# PortBreakoutCapacitive_r4_no_user.net
KiCad netlist of a schematic drawn in EAGLE
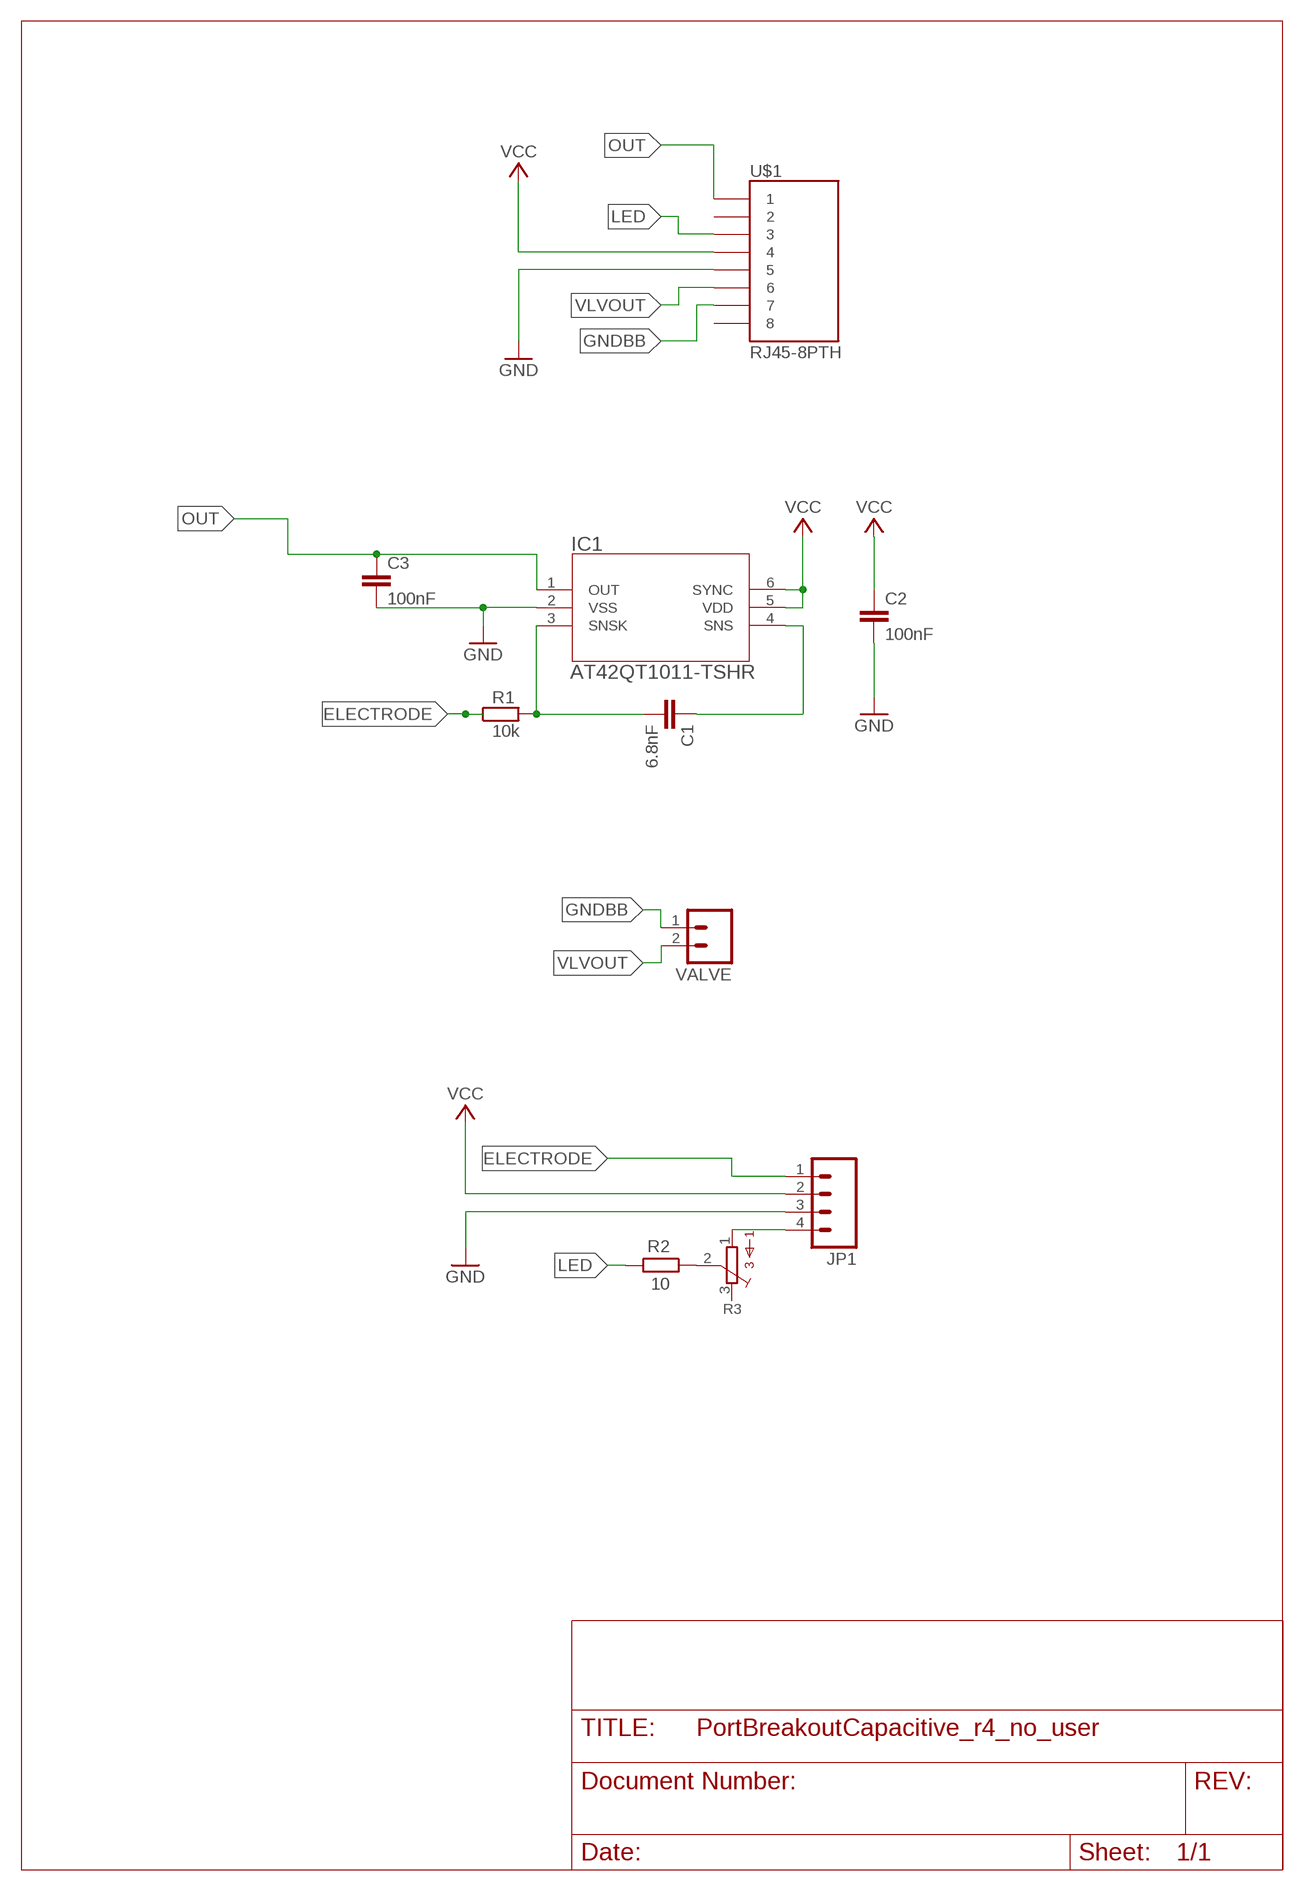
[diagram p0: schematic, sheet 1]

(export (version "E")
  (design (tool "Eeschema 10.0.6"))
  (components
    (comp (ref "C1")
      (value "6.8nF")
      (footprint "eagle-import:C1206")
      (libsource (lib "eagle-import") (part "C-EUC1206"))
    )
    (comp (ref "C2")
      (value "100nF")
      (footprint "eagle-import:C1206")
      (libsource (lib "eagle-import") (part "C-EUC1206"))
    )
    (comp (ref "C3")
      (value "100nF")
      (footprint "eagle-import:C1206")
      (libsource (lib "eagle-import") (part "C-EUC1206"))
    )
    (comp (ref "IC1")
      (value "AT42QT1011-TSHR")
      (footprint "eagle-import:6ST1_ATM")
      (fields (field (name "MANUFACTURER_PART_NUMBER") "AT42QT1010-TSHR"))
      (libsource (lib "eagle-import") (part "AT42QT1010-TSHR"))
    )
    (comp (ref "JP1")
      (value "CONN_04SCREW")
      (footprint "eagle-import:SCREWTERMINAL-3.5MM-4")
      (libsource (lib "eagle-import") (part "CONN_04SCREW"))
    )
    (comp (ref "R1")
      (value "10k")
      (footprint "eagle-import:R1206")
      (libsource (lib "eagle-import") (part "R-EU_R1206"))
    )
    (comp (ref "R2")
      (value "10")
      (footprint "eagle-import:R1206")
      (libsource (lib "eagle-import") (part "R-EU_R1206"))
    )
    (comp (ref "R3")
      (value "3362R")
      (footprint "eagle-import:3362R")
      (libsource (lib "eagle-import") (part "3362R"))
    )
    (comp (ref "U$1")
      (value "RJ45-8PTH")
      (footprint "eagle-import:RJ45-8")
      (libsource (lib "eagle-import") (part "RJ45-8PTH"))
    )
    (comp (ref "VALVE")
      (value "M023.5MM_LOCK")
      (footprint "eagle-import:SCREWTERMINAL-3.5MM-2_LOCK")
      (libsource (lib "eagle-import") (part "M023.5MM_LOCK"))
    )
  )
  (nets
    (net (code "1") (name "ELECTRODE") (class "Default")
      (node (ref "JP1") (pin "1") (pinfunction "1_1") (pintype "passive"))
      (node (ref "R1") (pin "1") (pinfunction "1_1") (pintype "passive"))
    )
    (net (code "2") (name "GND") (class "Default")
      (node (ref "C2") (pin "2") (pinfunction "2_2") (pintype "passive"))
      (node (ref "C3") (pin "2") (pinfunction "2_2") (pintype "passive"))
      (node (ref "IC1") (pin "2") (pinfunction "VSS_2") (pintype "power_in"))
      (node (ref "JP1") (pin "3") (pinfunction "3_3") (pintype "passive"))
      (node (ref "U$1") (pin "5") (pinfunction "5_5") (pintype "bidirectional"))
    )
    (net (code "3") (name "GNDBB") (class "Default")
      (node (ref "U$1") (pin "7") (pinfunction "7_7") (pintype "bidirectional"))
      (node (ref "VALVE") (pin "1") (pinfunction "1_1") (pintype "passive"))
    )
    (net (code "4") (name "LED") (class "Default")
      (node (ref "R2") (pin "2") (pinfunction "2_2") (pintype "passive"))
      (node (ref "U$1") (pin "3") (pinfunction "3_3") (pintype "bidirectional"))
    )
    (net (code "5") (name "Net-(IC1-SNS)") (class "Default")
      (node (ref "C1") (pin "1") (pinfunction "1_1") (pintype "passive"))
      (node (ref "IC1") (pin "4") (pinfunction "SNS_4") (pintype "bidirectional"))
    )
    (net (code "6") (name "Net-(IC1-SNSK)") (class "Default")
      (node (ref "C1") (pin "2") (pinfunction "2_2") (pintype "passive"))
      (node (ref "IC1") (pin "3") (pinfunction "SNSK_3") (pintype "bidirectional"))
      (node (ref "R1") (pin "2") (pinfunction "2_2") (pintype "passive"))
    )
    (net (code "7") (name "Net-(JP1-Pad4)") (class "Default")
      (node (ref "JP1") (pin "4") (pinfunction "4_4") (pintype "passive"))
      (node (ref "R3") (pin "1") (pinfunction "1_1") (pintype "passive"))
    )
    (net (code "8") (name "Net-(R2-Pad1)") (class "Default")
      (node (ref "R2") (pin "1") (pinfunction "1_1") (pintype "passive"))
      (node (ref "R3") (pin "2") (pinfunction "2_2") (pintype "passive"))
    )
    (net (code "9") (name "OUT") (class "Default")
      (node (ref "C3") (pin "1") (pinfunction "1_1") (pintype "passive"))
      (node (ref "IC1") (pin "1") (pinfunction "OUT_1") (pintype "output"))
      (node (ref "U$1") (pin "1") (pinfunction "1_1") (pintype "bidirectional"))
    )
    (net (code "10") (name "VCC") (class "Default")
      (node (ref "C2") (pin "1") (pinfunction "1_1") (pintype "passive"))
      (node (ref "IC1") (pin "5") (pinfunction "VDD_5") (pintype "power_in"))
      (node (ref "IC1") (pin "6") (pinfunction "SYNC_6") (pintype "input"))
      (node (ref "JP1") (pin "2") (pinfunction "2_2") (pintype "passive"))
      (node (ref "U$1") (pin "4") (pinfunction "4_4") (pintype "bidirectional"))
    )
    (net (code "11") (name "VLVOUT") (class "Default")
      (node (ref "U$1") (pin "6") (pinfunction "6_6") (pintype "bidirectional"))
      (node (ref "VALVE") (pin "2") (pinfunction "2_2") (pintype "passive"))
    )
    (net (code "12") (name "unconnected-(R3-Pad3)") (class "Default")
      (node (ref "R3") (pin "3") (pinfunction "3_3") (pintype "passive"))
    )
    (net (code "13") (name "unconnected-(U$1-Pad2)") (class "Default")
      (node (ref "U$1") (pin "2") (pinfunction "2_2") (pintype "bidirectional"))
    )
    (net (code "14") (name "unconnected-(U$1-Pad8)") (class "Default")
      (node (ref "U$1") (pin "8") (pinfunction "8_8") (pintype "bidirectional"))
    )
  )
)
